# design.net
KiCad netlist of a schematic drawn in Altium Designer
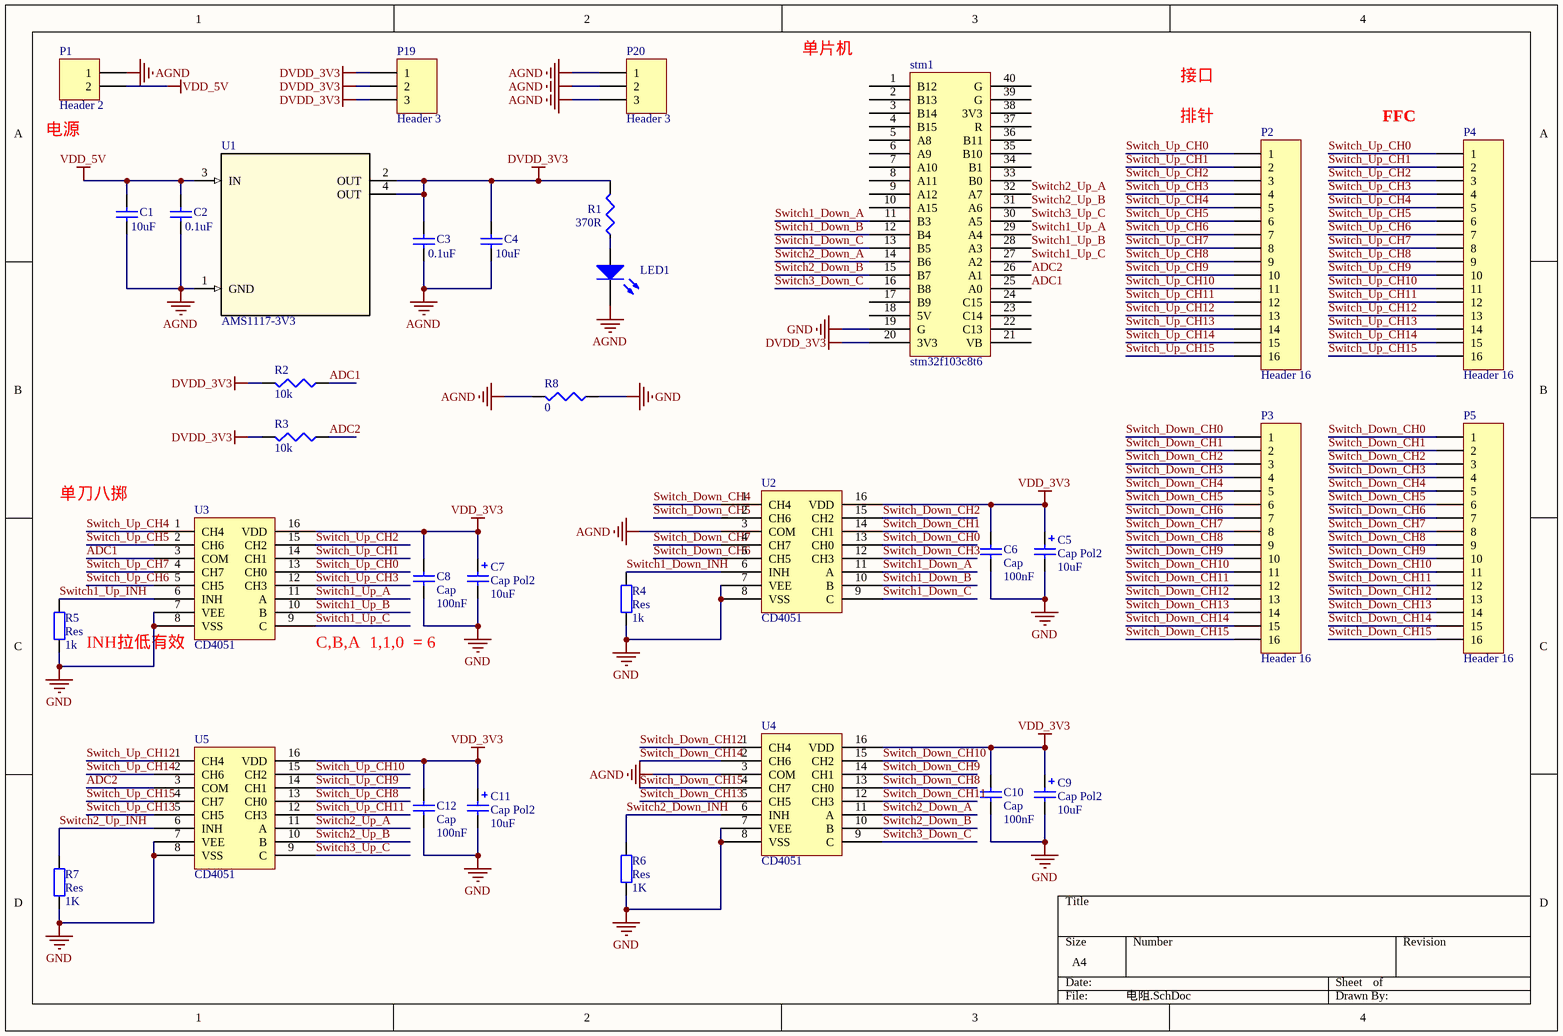
[diagram p0: 电阻.SchDoc]

(export (version "E")
  (design (tool "Eeschema 10.0.6"))
  (components
    (comp (ref "C1")
      (value "10uF")
      (footprint "C-0603")
      (description "Capacitor (Semiconductor SIM Model)")
      (fields (field (name "PUBLISHER") "Altium Limited"))
      (libsource (lib "Miscellaneous Devices") (part "Cap Semi"))
    )
    (comp (ref "C2")
      (value "0.1uF")
      (footprint "C-0603")
      (description "Capacitor (Semiconductor SIM Model)")
      (fields (field (name "PUBLISHER") "Altium Limited"))
      (libsource (lib "Miscellaneous Devices") (part "Cap Semi"))
    )
    (comp (ref "C3")
      (value "0.1uF")
      (footprint "C-0603")
      (description "Capacitor (Semiconductor SIM Model)")
      (fields (field (name "PUBLISHER") "Altium Limited"))
      (libsource (lib "Miscellaneous Devices") (part "Cap Semi"))
    )
    (comp (ref "C4")
      (value "10uF")
      (footprint "C-0603")
      (description "Capacitor (Semiconductor SIM Model)")
      (fields (field (name "PUBLISHER") "Altium Limited"))
      (libsource (lib "Miscellaneous Devices") (part "Cap Semi"))
    )
    (comp (ref "C5")
      (value "Cap Pol2")
      (footprint "Cap-TA")
      (description "Polarized Capacitor (Axial)")
      (fields (field (name "ALTIUM_VALUE") "10uF") (field (name "PUBLISHER") "Altium Limited"))
      (libsource (lib "YD-LibrarySCH") (part "Cap Pol2"))
    )
    (comp (ref "C6")
      (value "Cap")
      (footprint "0805C")
      (description "Capacitor")
      (fields (field (name "ALTIUM_VALUE") "100nF") (field (name "PUBLISHER") "Altium Limited"))
      (libsource (lib "YD-LibrarySCH") (part "Cap"))
    )
    (comp (ref "C7")
      (value "Cap Pol2")
      (footprint "Cap-TA")
      (description "Polarized Capacitor (Axial)")
      (fields (field (name "ALTIUM_VALUE") "10uF") (field (name "PUBLISHER") "Altium Limited"))
      (libsource (lib "YD-LibrarySCH") (part "Cap Pol2"))
    )
    (comp (ref "C8")
      (value "Cap")
      (footprint "0805C")
      (description "Capacitor")
      (fields (field (name "ALTIUM_VALUE") "100nF") (field (name "PUBLISHER") "Altium Limited"))
      (libsource (lib "YD-LibrarySCH") (part "Cap"))
    )
    (comp (ref "C9")
      (value "Cap Pol2")
      (footprint "Cap-TA")
      (description "Polarized Capacitor (Axial)")
      (fields (field (name "ALTIUM_VALUE") "10uF") (field (name "PUBLISHER") "Altium Limited"))
      (libsource (lib "YD-LibrarySCH") (part "Cap Pol2"))
    )
    (comp (ref "C10")
      (value "Cap")
      (footprint "0805C")
      (description "Capacitor")
      (fields (field (name "ALTIUM_VALUE") "100nF") (field (name "PUBLISHER") "Altium Limited"))
      (libsource (lib "YD-LibrarySCH") (part "Cap"))
    )
    (comp (ref "C11")
      (value "Cap Pol2")
      (footprint "Cap-TA")
      (description "Polarized Capacitor (Axial)")
      (fields (field (name "ALTIUM_VALUE") "10uF") (field (name "PUBLISHER") "Altium Limited"))
      (libsource (lib "YD-LibrarySCH") (part "Cap Pol2"))
    )
    (comp (ref "C12")
      (value "Cap")
      (footprint "0805C")
      (description "Capacitor")
      (fields (field (name "ALTIUM_VALUE") "100nF") (field (name "PUBLISHER") "Altium Limited"))
      (libsource (lib "YD-LibrarySCH") (part "Cap"))
    )
    (comp (ref "LED1")
      (value "~")
      (footprint "CLED1608-0603")
      (description "Typical Chip LED")
      (fields (field (name "PUBLISHER") "Altium Limited"))
      (libsource (lib "EButterflyIntegratedLibrary") (part "LED Chip"))
    )
    (comp (ref "P1")
      (value "Header 2")
      (footprint "XH2.54-LI-2P")
      (description "Header, 2-Pin")
      (fields (field (name "PUBLISHER") "Altium Limited"))
      (libsource (lib "Miscellaneous Connectors") (part "Header 2"))
    )
    (comp (ref "P2")
      (value "Header 16")
      (footprint "HDR1X16")
      (description "Header, 16-Pin")
      (fields (field (name "PUBLISHER") "Altium Limited"))
      (libsource (lib "Miscellaneous Connectors") (part "Header 16"))
    )
    (comp (ref "P3")
      (value "Header 16")
      (footprint "HDR1X16")
      (description "Header, 16-Pin")
      (fields (field (name "PUBLISHER") "Altium Limited"))
      (libsource (lib "Miscellaneous Connectors") (part "Header 16"))
    )
    (comp (ref "P4")
      (value "Header 16")
      (footprint "ffc_1mm")
      (description "Header, 16-Pin")
      (fields (field (name "PUBLISHER") "Altium Limited"))
      (libsource (lib "Miscellaneous Connectors") (part "Header 16"))
    )
    (comp (ref "P5")
      (value "Header 16")
      (footprint "ffc_1mm")
      (description "Header, 16-Pin")
      (fields (field (name "PUBLISHER") "Altium Limited"))
      (libsource (lib "Miscellaneous Connectors") (part "Header 16"))
    )
    (comp (ref "P19")
      (value "Header 3")
      (footprint "HDR1X3")
      (description "Header, 3-Pin")
      (fields (field (name "PUBLISHER") "Altium Limited"))
      (libsource (lib "Miscellaneous Connectors") (part "Header 3"))
    )
    (comp (ref "P20")
      (value "Header 3")
      (footprint "HDR1X3")
      (description "Header, 3-Pin")
      (fields (field (name "PUBLISHER") "Altium Limited"))
      (libsource (lib "Miscellaneous Connectors") (part "Header 3"))
    )
    (comp (ref "R1")
      (value "370R")
      (footprint "R-0603")
      (description "Resistor")
      (fields (field (name "Comment") "Res3") (field (name "PUBLISHER") "Altium Limited"))
      (libsource (lib "Miscellaneous Devices") (part "Res3"))
    )
    (comp (ref "R2")
      (value "10k")
      (footprint "R-0603")
      (description "Resistor")
      (fields (field (name "Comment") "Res3") (field (name "PUBLISHER") "Altium Limited"))
      (libsource (lib "Miscellaneous Devices") (part "Res3"))
    )
    (comp (ref "R3")
      (value "10k")
      (footprint "R-0603")
      (description "Resistor")
      (fields (field (name "Comment") "Res3") (field (name "PUBLISHER") "Altium Limited"))
      (libsource (lib "Miscellaneous Devices") (part "Res3"))
    )
    (comp (ref "R4")
      (value "Res")
      (footprint "0805R")
      (description "Resistor")
      (fields (field (name "ALTIUM_VALUE") "1k") (field (name "PUBLISHER") "Altium Limited"))
      (libsource (lib "YD-LibrarySCH") (part "Res"))
    )
    (comp (ref "R5")
      (value "Res")
      (footprint "0805R")
      (description "Resistor")
      (fields (field (name "ALTIUM_VALUE") "1k") (field (name "PUBLISHER") "Altium Limited"))
      (libsource (lib "YD-LibrarySCH") (part "Res"))
    )
    (comp (ref "R6")
      (value "Res")
      (footprint "0805R")
      (description "Resistor")
      (fields (field (name "ALTIUM_VALUE") "1K") (field (name "PUBLISHER") "Altium Limited"))
      (libsource (lib "YD-LibrarySCH") (part "Res"))
    )
    (comp (ref "R7")
      (value "Res")
      (footprint "0805R")
      (description "Resistor")
      (fields (field (name "ALTIUM_VALUE") "1K") (field (name "PUBLISHER") "Altium Limited"))
      (libsource (lib "YD-LibrarySCH") (part "Res"))
    )
    (comp (ref "R8")
      (value "0")
      (footprint "R-0603")
      (description "Resistor")
      (fields (field (name "Comment") "Res3") (field (name "PUBLISHER") "Altium Limited"))
      (libsource (lib "Miscellaneous Devices") (part "Res3"))
    )
    (comp (ref "stm1")
      (value "stm32f103c8t6")
      (footprint "PCBComponent_1")
      (libsource (lib "Schlib1") (part "stm32f103c8t6"))
    )
    (comp (ref "U1")
      (value "AMS1117-3V3")
      (footprint "LM317")
      (description "LM317DCYR-SOT223")
      (fields
        (field (name "PARTNUMBER") "LM317DCYR")
        (field (name "ALTERNATE_PARTNUMBER") "LM317DCY")
        (field (name "SYMBOLCREATER") "Altium")
      )
      (libsource (lib "LM317") (part "LM317DCYR"))
    )
    (comp (ref "U2") (value "CD4051") (footprint "SO16") (libsource (lib "YD-LibrarySCH") (part "CD4051")))
    (comp (ref "U3") (value "CD4051") (footprint "SO16") (libsource (lib "YD-LibrarySCH") (part "CD4051")))
    (comp (ref "U4") (value "CD4051") (footprint "SO16") (libsource (lib "YD-LibrarySCH") (part "CD4051")))
    (comp (ref "U5") (value "CD4051") (footprint "SO16") (libsource (lib "YD-LibrarySCH") (part "CD4051")))
  )
  (nets
    (net (code "1") (name "/ADC1") (class "Default")
      (node (ref "R2") (pin "1") (pinfunction "1_1") (pintype "passive"))
      (node (ref "U3") (pin "3") (pinfunction "COM_3") (pintype "passive"))
      (node (ref "stm1") (pin "25") (pinfunction "A0_25") (pintype "passive"))
    )
    (net (code "2") (name "/ADC2") (class "Default")
      (node (ref "R3") (pin "1") (pinfunction "1_1") (pintype "passive"))
      (node (ref "U5") (pin "3") (pinfunction "COM_3") (pintype "passive"))
      (node (ref "stm1") (pin "26") (pinfunction "A1_26") (pintype "passive"))
    )
    (net (code "6") (name "/Switch1_Down_A") (class "Default")
      (node (ref "U2") (pin "11") (pinfunction "A_11") (pintype "passive"))
      (node (ref "stm1") (pin "11") (pinfunction "B3_11") (pintype "passive"))
    )
    (net (code "7") (name "/Switch1_Down_B") (class "Default")
      (node (ref "U2") (pin "10") (pinfunction "B_10") (pintype "passive"))
      (node (ref "stm1") (pin "12") (pinfunction "B4_12") (pintype "passive"))
    )
    (net (code "8") (name "/Switch1_Down_C") (class "Default")
      (node (ref "U2") (pin "9") (pinfunction "C_9") (pintype "passive"))
      (node (ref "stm1") (pin "13") (pinfunction "B5_13") (pintype "passive"))
    )
    (net (code "9") (name "/Switch1_Down_INH") (class "Default")
      (node (ref "R4") (pin "2") (pinfunction "2_2") (pintype "passive"))
      (node (ref "U2") (pin "6") (pinfunction "INH_6") (pintype "passive"))
    )
    (net (code "10") (name "/Switch1_Up_A") (class "Default")
      (node (ref "U3") (pin "11") (pinfunction "A_11") (pintype "passive"))
      (node (ref "stm1") (pin "29") (pinfunction "A4_29") (pintype "passive"))
    )
    (net (code "11") (name "/Switch1_Up_B") (class "Default")
      (node (ref "U3") (pin "10") (pinfunction "B_10") (pintype "passive"))
      (node (ref "stm1") (pin "28") (pinfunction "A3_28") (pintype "passive"))
    )
    (net (code "12") (name "/Switch1_Up_C") (class "Default")
      (node (ref "U3") (pin "9") (pinfunction "C_9") (pintype "passive"))
      (node (ref "stm1") (pin "27") (pinfunction "A2_27") (pintype "passive"))
    )
    (net (code "13") (name "/Switch1_Up_INH") (class "Default")
      (node (ref "R5") (pin "2") (pinfunction "2_2") (pintype "passive"))
      (node (ref "U3") (pin "6") (pinfunction "INH_6") (pintype "passive"))
    )
    (net (code "14") (name "/Switch2_Down_A") (class "Default")
      (node (ref "U4") (pin "11") (pinfunction "A_11") (pintype "passive"))
      (node (ref "stm1") (pin "14") (pinfunction "B6_14") (pintype "passive"))
    )
    (net (code "15") (name "/Switch2_Down_B") (class "Default")
      (node (ref "U4") (pin "10") (pinfunction "B_10") (pintype "passive"))
      (node (ref "stm1") (pin "15") (pinfunction "B7_15") (pintype "passive"))
    )
    (net (code "16") (name "/Switch2_Down_INH") (class "Default")
      (node (ref "R6") (pin "2") (pinfunction "2_2") (pintype "passive"))
      (node (ref "U4") (pin "6") (pinfunction "INH_6") (pintype "passive"))
    )
    (net (code "17") (name "/Switch2_Up_A") (class "Default")
      (node (ref "U5") (pin "11") (pinfunction "A_11") (pintype "passive"))
      (node (ref "stm1") (pin "32") (pinfunction "A7_32") (pintype "passive"))
    )
    (net (code "18") (name "/Switch2_Up_B") (class "Default")
      (node (ref "U5") (pin "10") (pinfunction "B_10") (pintype "passive"))
      (node (ref "stm1") (pin "31") (pinfunction "A6_31") (pintype "passive"))
    )
    (net (code "19") (name "/Switch2_Up_INH") (class "Default")
      (node (ref "R7") (pin "2") (pinfunction "2_2") (pintype "passive"))
      (node (ref "U5") (pin "6") (pinfunction "INH_6") (pintype "passive"))
    )
    (net (code "20") (name "/Switch3_Down_C") (class "Default")
      (node (ref "U4") (pin "9") (pinfunction "C_9") (pintype "passive"))
      (node (ref "stm1") (pin "16") (pinfunction "B8_16") (pintype "passive"))
    )
    (net (code "21") (name "/Switch3_Up_C") (class "Default")
      (node (ref "U5") (pin "9") (pinfunction "C_9") (pintype "passive"))
      (node (ref "stm1") (pin "30") (pinfunction "A5_30") (pintype "passive"))
    )
    (net (code "22") (name "/Switch_Down_CH0") (class "Default")
      (node (ref "P3") (pin "1") (pinfunction "1_1") (pintype "passive"))
      (node (ref "P5") (pin "1") (pinfunction "1_1") (pintype "passive"))
      (node (ref "U2") (pin "13") (pinfunction "CH0_13") (pintype "passive"))
    )
    (net (code "23") (name "/Switch_Down_CH1") (class "Default")
      (node (ref "P3") (pin "2") (pinfunction "2_2") (pintype "passive"))
      (node (ref "P5") (pin "2") (pinfunction "2_2") (pintype "passive"))
      (node (ref "U2") (pin "14") (pinfunction "CH1_14") (pintype "passive"))
    )
    (net (code "24") (name "/Switch_Down_CH2") (class "Default")
      (node (ref "P3") (pin "3") (pinfunction "3_3") (pintype "passive"))
      (node (ref "P5") (pin "3") (pinfunction "3_3") (pintype "passive"))
      (node (ref "U2") (pin "15") (pinfunction "CH2_15") (pintype "passive"))
    )
    (net (code "25") (name "/Switch_Down_CH3") (class "Default")
      (node (ref "P3") (pin "4") (pinfunction "4_4") (pintype "passive"))
      (node (ref "P5") (pin "4") (pinfunction "4_4") (pintype "passive"))
      (node (ref "U2") (pin "12") (pinfunction "CH3_12") (pintype "passive"))
    )
    (net (code "26") (name "/Switch_Down_CH4") (class "Default")
      (node (ref "P3") (pin "5") (pinfunction "5_5") (pintype "passive"))
      (node (ref "P5") (pin "5") (pinfunction "5_5") (pintype "passive"))
      (node (ref "U2") (pin "1") (pinfunction "CH4_1") (pintype "passive"))
    )
    (net (code "27") (name "/Switch_Down_CH5") (class "Default")
      (node (ref "P3") (pin "6") (pinfunction "6_6") (pintype "passive"))
      (node (ref "P5") (pin "6") (pinfunction "6_6") (pintype "passive"))
      (node (ref "U2") (pin "2") (pinfunction "CH6_2") (pintype "passive"))
    )
    (net (code "28") (name "/Switch_Down_CH6") (class "Default")
      (node (ref "P3") (pin "7") (pinfunction "7_7") (pintype "passive"))
      (node (ref "P5") (pin "7") (pinfunction "7_7") (pintype "passive"))
      (node (ref "U2") (pin "5") (pinfunction "CH5_5") (pintype "passive"))
    )
    (net (code "29") (name "/Switch_Down_CH7") (class "Default")
      (node (ref "P3") (pin "8") (pinfunction "8_8") (pintype "passive"))
      (node (ref "P5") (pin "8") (pinfunction "8_8") (pintype "passive"))
      (node (ref "U2") (pin "4") (pinfunction "CH7_4") (pintype "passive"))
    )
    (net (code "30") (name "/Switch_Down_CH8") (class "Default")
      (node (ref "P3") (pin "9") (pinfunction "9_9") (pintype "passive"))
      (node (ref "P5") (pin "9") (pinfunction "9_9") (pintype "passive"))
      (node (ref "U4") (pin "13") (pinfunction "CH0_13") (pintype "passive"))
    )
    (net (code "31") (name "/Switch_Down_CH9") (class "Default")
      (node (ref "P3") (pin "10") (pinfunction "10_10") (pintype "passive"))
      (node (ref "P5") (pin "10") (pinfunction "10_10") (pintype "passive"))
      (node (ref "U4") (pin "14") (pinfunction "CH1_14") (pintype "passive"))
    )
    (net (code "32") (name "/Switch_Down_CH10") (class "Default")
      (node (ref "P3") (pin "11") (pinfunction "11_11") (pintype "passive"))
      (node (ref "P5") (pin "11") (pinfunction "11_11") (pintype "passive"))
      (node (ref "U4") (pin "15") (pinfunction "CH2_15") (pintype "passive"))
    )
    (net (code "33") (name "/Switch_Down_CH11") (class "Default")
      (node (ref "P3") (pin "12") (pinfunction "12_12") (pintype "passive"))
      (node (ref "P5") (pin "12") (pinfunction "12_12") (pintype "passive"))
      (node (ref "U4") (pin "12") (pinfunction "CH3_12") (pintype "passive"))
    )
    (net (code "34") (name "/Switch_Down_CH12") (class "Default")
      (node (ref "P3") (pin "13") (pinfunction "13_13") (pintype "passive"))
      (node (ref "P5") (pin "13") (pinfunction "13_13") (pintype "passive"))
      (node (ref "U4") (pin "1") (pinfunction "CH4_1") (pintype "passive"))
    )
    (net (code "35") (name "/Switch_Down_CH13") (class "Default")
      (node (ref "P3") (pin "14") (pinfunction "14_14") (pintype "passive"))
      (node (ref "P5") (pin "14") (pinfunction "14_14") (pintype "passive"))
      (node (ref "U4") (pin "5") (pinfunction "CH5_5") (pintype "passive"))
    )
    (net (code "36") (name "/Switch_Down_CH14") (class "Default")
      (node (ref "P3") (pin "15") (pinfunction "15_15") (pintype "passive"))
      (node (ref "P5") (pin "15") (pinfunction "15_15") (pintype "passive"))
      (node (ref "U4") (pin "2") (pinfunction "CH6_2") (pintype "passive"))
    )
    (net (code "37") (name "/Switch_Down_CH15") (class "Default")
      (node (ref "P3") (pin "16") (pinfunction "16_16") (pintype "passive"))
      (node (ref "P5") (pin "16") (pinfunction "16_16") (pintype "passive"))
      (node (ref "U4") (pin "4") (pinfunction "CH7_4") (pintype "passive"))
    )
    (net (code "38") (name "/Switch_Up_CH0") (class "Default")
      (node (ref "P2") (pin "1") (pinfunction "1_1") (pintype "passive"))
      (node (ref "P4") (pin "1") (pinfunction "1_1") (pintype "passive"))
      (node (ref "U3") (pin "13") (pinfunction "CH0_13") (pintype "passive"))
    )
    (net (code "39") (name "/Switch_Up_CH1") (class "Default")
      (node (ref "P2") (pin "2") (pinfunction "2_2") (pintype "passive"))
      (node (ref "P4") (pin "2") (pinfunction "2_2") (pintype "passive"))
      (node (ref "U3") (pin "14") (pinfunction "CH1_14") (pintype "passive"))
    )
    (net (code "40") (name "/Switch_Up_CH2") (class "Default")
      (node (ref "P2") (pin "3") (pinfunction "3_3") (pintype "passive"))
      (node (ref "P4") (pin "3") (pinfunction "3_3") (pintype "passive"))
      (node (ref "U3") (pin "15") (pinfunction "CH2_15") (pintype "passive"))
    )
    (net (code "41") (name "/Switch_Up_CH3") (class "Default")
      (node (ref "P2") (pin "4") (pinfunction "4_4") (pintype "passive"))
      (node (ref "P4") (pin "4") (pinfunction "4_4") (pintype "passive"))
      (node (ref "U3") (pin "12") (pinfunction "CH3_12") (pintype "passive"))
    )
    (net (code "42") (name "/Switch_Up_CH4") (class "Default")
      (node (ref "P2") (pin "5") (pinfunction "5_5") (pintype "passive"))
      (node (ref "P4") (pin "5") (pinfunction "5_5") (pintype "passive"))
      (node (ref "U3") (pin "1") (pinfunction "CH4_1") (pintype "passive"))
    )
    (net (code "43") (name "/Switch_Up_CH5") (class "Default")
      (node (ref "P2") (pin "6") (pinfunction "6_6") (pintype "passive"))
      (node (ref "P4") (pin "6") (pinfunction "6_6") (pintype "passive"))
      (node (ref "U3") (pin "2") (pinfunction "CH6_2") (pintype "passive"))
    )
    (net (code "44") (name "/Switch_Up_CH6") (class "Default")
      (node (ref "P2") (pin "7") (pinfunction "7_7") (pintype "passive"))
      (node (ref "P4") (pin "7") (pinfunction "7_7") (pintype "passive"))
      (node (ref "U3") (pin "5") (pinfunction "CH5_5") (pintype "passive"))
    )
    (net (code "45") (name "/Switch_Up_CH7") (class "Default")
      (node (ref "P2") (pin "8") (pinfunction "8_8") (pintype "passive"))
      (node (ref "P4") (pin "8") (pinfunction "8_8") (pintype "passive"))
      (node (ref "U3") (pin "4") (pinfunction "CH7_4") (pintype "passive"))
    )
    (net (code "46") (name "/Switch_Up_CH8") (class "Default")
      (node (ref "P2") (pin "9") (pinfunction "9_9") (pintype "passive"))
      (node (ref "P4") (pin "9") (pinfunction "9_9") (pintype "passive"))
      (node (ref "U5") (pin "13") (pinfunction "CH0_13") (pintype "passive"))
    )
    (net (code "47") (name "/Switch_Up_CH9") (class "Default")
      (node (ref "P2") (pin "10") (pinfunction "10_10") (pintype "passive"))
      (node (ref "P4") (pin "10") (pinfunction "10_10") (pintype "passive"))
      (node (ref "U5") (pin "14") (pinfunction "CH1_14") (pintype "passive"))
    )
    (net (code "48") (name "/Switch_Up_CH10") (class "Default")
      (node (ref "P2") (pin "11") (pinfunction "11_11") (pintype "passive"))
      (node (ref "P4") (pin "11") (pinfunction "11_11") (pintype "passive"))
      (node (ref "U5") (pin "15") (pinfunction "CH2_15") (pintype "passive"))
    )
    (net (code "49") (name "/Switch_Up_CH11") (class "Default")
      (node (ref "P2") (pin "12") (pinfunction "12_12") (pintype "passive"))
      (node (ref "P4") (pin "12") (pinfunction "12_12") (pintype "passive"))
      (node (ref "U5") (pin "12") (pinfunction "CH3_12") (pintype "passive"))
    )
    (net (code "50") (name "/Switch_Up_CH12") (class "Default")
      (node (ref "P2") (pin "13") (pinfunction "13_13") (pintype "passive"))
      (node (ref "P4") (pin "13") (pinfunction "13_13") (pintype "passive"))
      (node (ref "U5") (pin "1") (pinfunction "CH4_1") (pintype "passive"))
    )
    (net (code "51") (name "/Switch_Up_CH13") (class "Default")
      (node (ref "P2") (pin "14") (pinfunction "14_14") (pintype "passive"))
      (node (ref "P4") (pin "14") (pinfunction "14_14") (pintype "passive"))
      (node (ref "U5") (pin "5") (pinfunction "CH5_5") (pintype "passive"))
    )
    (net (code "52") (name "/Switch_Up_CH14") (class "Default")
      (node (ref "P2") (pin "15") (pinfunction "15_15") (pintype "passive"))
      (node (ref "P4") (pin "15") (pinfunction "15_15") (pintype "passive"))
      (node (ref "U5") (pin "2") (pinfunction "CH6_2") (pintype "passive"))
    )
    (net (code "53") (name "/Switch_Up_CH15") (class "Default")
      (node (ref "P2") (pin "16") (pinfunction "16_16") (pintype "passive"))
      (node (ref "P4") (pin "16") (pinfunction "16_16") (pintype "passive"))
      (node (ref "U5") (pin "4") (pinfunction "CH7_4") (pintype "passive"))
    )
    (net (code "59") (name "AGND") (class "Default")
      (node (ref "C1") (pin "1") (pinfunction "1_1") (pintype "passive"))
      (node (ref "C2") (pin "1") (pinfunction "1_1") (pintype "passive"))
      (node (ref "C3") (pin "1") (pinfunction "1_1") (pintype "passive"))
      (node (ref "C4") (pin "1") (pinfunction "1_1") (pintype "passive"))
      (node (ref "LED1") (pin "2") (pinfunction "K_2") (pintype "passive"))
      (node (ref "P1") (pin "1") (pinfunction "1_1") (pintype "passive"))
      (node (ref "P20") (pin "1") (pinfunction "1_1") (pintype "passive"))
      (node (ref "P20") (pin "2") (pinfunction "2_2") (pintype "passive"))
      (node (ref "P20") (pin "3") (pinfunction "3_3") (pintype "passive"))
      (node (ref "R8") (pin "2") (pinfunction "2_2") (pintype "passive"))
      (node (ref "U1") (pin "1") (pinfunction "GND_1") (pintype "input"))
      (node (ref "U2") (pin "3") (pinfunction "COM_3") (pintype "passive"))
      (node (ref "U4") (pin "3") (pinfunction "COM_3") (pintype "passive"))
    )
    (net (code "60") (name "DVDD_3V3") (class "Default")
      (node (ref "C3") (pin "2") (pinfunction "2_2") (pintype "passive"))
      (node (ref "C4") (pin "2") (pinfunction "2_2") (pintype "passive"))
      (node (ref "P19") (pin "1") (pinfunction "1_1") (pintype "passive"))
      (node (ref "P19") (pin "2") (pinfunction "2_2") (pintype "passive"))
      (node (ref "P19") (pin "3") (pinfunction "3_3") (pintype "passive"))
      (node (ref "R1") (pin "2") (pinfunction "2_2") (pintype "passive"))
      (node (ref "R2") (pin "2") (pinfunction "2_2") (pintype "passive"))
      (node (ref "R3") (pin "2") (pinfunction "2_2") (pintype "passive"))
      (node (ref "U1") (pin "2") (pinfunction "OUT_2") (pintype "passive"))
      (node (ref "U1") (pin "4") (pinfunction "OUT_4") (pintype "passive"))
      (node (ref "stm1") (pin "20") (pinfunction "3V3_20") (pintype "passive"))
    )
    (net (code "61") (name "GND") (class "Default")
      (node (ref "C10") (pin "1") (pinfunction "1_1") (pintype "passive"))
      (node (ref "C11") (pin "2") (pinfunction "2_2") (pintype "passive"))
      (node (ref "C12") (pin "1") (pinfunction "1_1") (pintype "passive"))
      (node (ref "C5") (pin "2") (pinfunction "2_2") (pintype "passive"))
      (node (ref "C6") (pin "1") (pinfunction "1_1") (pintype "passive"))
      (node (ref "C7") (pin "2") (pinfunction "2_2") (pintype "passive"))
      (node (ref "C8") (pin "1") (pinfunction "1_1") (pintype "passive"))
      (node (ref "C9") (pin "2") (pinfunction "2_2") (pintype "passive"))
      (node (ref "R4") (pin "1") (pinfunction "1_1") (pintype "passive"))
      (node (ref "R5") (pin "1") (pinfunction "1_1") (pintype "passive"))
      (node (ref "R6") (pin "1") (pinfunction "1_1") (pintype "passive"))
      (node (ref "R7") (pin "1") (pinfunction "1_1") (pintype "passive"))
      (node (ref "R8") (pin "1") (pinfunction "1_1") (pintype "passive"))
      (node (ref "U2") (pin "7") (pinfunction "VEE_7") (pintype "passive"))
      (node (ref "U2") (pin "8") (pinfunction "VSS_8") (pintype "passive"))
      (node (ref "U3") (pin "7") (pinfunction "VEE_7") (pintype "passive"))
      (node (ref "U3") (pin "8") (pinfunction "VSS_8") (pintype "passive"))
      (node (ref "U4") (pin "7") (pinfunction "VEE_7") (pintype "passive"))
      (node (ref "U4") (pin "8") (pinfunction "VSS_8") (pintype "passive"))
      (node (ref "U5") (pin "7") (pinfunction "VEE_7") (pintype "passive"))
      (node (ref "U5") (pin "8") (pinfunction "VSS_8") (pintype "passive"))
      (node (ref "stm1") (pin "19") (pinfunction "G_19") (pintype "passive"))
    )
    (net (code "62") (name "Net-(LED1-A)") (class "Default")
      (node (ref "LED1") (pin "1") (pinfunction "A_1") (pintype "passive"))
      (node (ref "R1") (pin "1") (pinfunction "1_1") (pintype "passive"))
    )
    (net (code "63") (name "VDD_3V3") (class "Default")
      (node (ref "C10") (pin "2") (pinfunction "2_2") (pintype "passive"))
      (node (ref "C11") (pin "1") (pinfunction "1_1") (pintype "passive"))
      (node (ref "C12") (pin "2") (pinfunction "2_2") (pintype "passive"))
      (node (ref "C5") (pin "1") (pinfunction "1_1") (pintype "passive"))
      (node (ref "C6") (pin "2") (pinfunction "2_2") (pintype "passive"))
      (node (ref "C7") (pin "1") (pinfunction "1_1") (pintype "passive"))
      (node (ref "C8") (pin "2") (pinfunction "2_2") (pintype "passive"))
      (node (ref "C9") (pin "1") (pinfunction "1_1") (pintype "passive"))
      (node (ref "U2") (pin "16") (pinfunction "VDD_16") (pintype "passive"))
      (node (ref "U3") (pin "16") (pinfunction "VDD_16") (pintype "passive"))
      (node (ref "U4") (pin "16") (pinfunction "VDD_16") (pintype "passive"))
      (node (ref "U5") (pin "16") (pinfunction "VDD_16") (pintype "passive"))
    )
    (net (code "64") (name "VDD_5V") (class "Default")
      (node (ref "C1") (pin "2") (pinfunction "2_2") (pintype "passive"))
      (node (ref "C2") (pin "2") (pinfunction "2_2") (pintype "passive"))
      (node (ref "P1") (pin "2") (pinfunction "2_2") (pintype "passive"))
      (node (ref "U1") (pin "3") (pinfunction "IN_3") (pintype "input"))
    )
    (net (code "65") (name "unconnected-(stm1-3V3-Pad38)") (class "Default")
      (node (ref "stm1") (pin "38") (pinfunction "3V3_38") (pintype "passive"))
    )
    (net (code "66") (name "unconnected-(stm1-5V-Pad18)") (class "Default")
      (node (ref "stm1") (pin "18") (pinfunction "5V_18") (pintype "passive"))
    )
    (net (code "67") (name "unconnected-(stm1-A8-Pad5)") (class "Default")
      (node (ref "stm1") (pin "5") (pinfunction "A8_5") (pintype "passive"))
    )
    (net (code "68") (name "unconnected-(stm1-A9-Pad6)") (class "Default")
      (node (ref "stm1") (pin "6") (pinfunction "A9_6") (pintype "passive"))
    )
    (net (code "69") (name "unconnected-(stm1-A10-Pad7)") (class "Default")
      (node (ref "stm1") (pin "7") (pinfunction "A10_7") (pintype "passive"))
    )
    (net (code "70") (name "unconnected-(stm1-A11-Pad8)") (class "Default")
      (node (ref "stm1") (pin "8") (pinfunction "A11_8") (pintype "passive"))
    )
    (net (code "71") (name "unconnected-(stm1-A12-Pad9)") (class "Default")
      (node (ref "stm1") (pin "9") (pinfunction "A12_9") (pintype "passive"))
    )
    (net (code "72") (name "unconnected-(stm1-A15-Pad10)") (class "Default")
      (node (ref "stm1") (pin "10") (pinfunction "A15_10") (pintype "passive"))
    )
    (net (code "73") (name "unconnected-(stm1-B0-Pad33)") (class "Default")
      (node (ref "stm1") (pin "33") (pinfunction "B0_33") (pintype "passive"))
    )
    (net (code "74") (name "unconnected-(stm1-B1-Pad34)") (class "Default")
      (node (ref "stm1") (pin "34") (pinfunction "B1_34") (pintype "passive"))
    )
    (net (code "75") (name "unconnected-(stm1-B9-Pad17)") (class "Default")
      (node (ref "stm1") (pin "17") (pinfunction "B9_17") (pintype "passive"))
    )
    (net (code "76") (name "unconnected-(stm1-B10-Pad35)") (class "Default")
      (node (ref "stm1") (pin "35") (pinfunction "B10_35") (pintype "passive"))
    )
    (net (code "77") (name "unconnected-(stm1-B11-Pad36)") (class "Default")
      (node (ref "stm1") (pin "36") (pinfunction "B11_36") (pintype "passive"))
    )
    (net (code "78") (name "unconnected-(stm1-B12-Pad1)") (class "Default")
      (node (ref "stm1") (pin "1") (pinfunction "B12_1") (pintype "passive"))
    )
    (net (code "79") (name "unconnected-(stm1-B13-Pad2)") (class "Default")
      (node (ref "stm1") (pin "2") (pinfunction "B13_2") (pintype "passive"))
    )
    (net (code "80") (name "unconnected-(stm1-B14-Pad3)") (class "Default")
      (node (ref "stm1") (pin "3") (pinfunction "B14_3") (pintype "passive"))
    )
    (net (code "81") (name "unconnected-(stm1-B15-Pad4)") (class "Default")
      (node (ref "stm1") (pin "4") (pinfunction "B15_4") (pintype "passive"))
    )
    (net (code "82") (name "unconnected-(stm1-C13-Pad22)") (class "Default")
      (node (ref "stm1") (pin "22") (pinfunction "C13_22") (pintype "passive"))
    )
    (net (code "83") (name "unconnected-(stm1-C14-Pad23)") (class "Default")
      (node (ref "stm1") (pin "23") (pinfunction "C14_23") (pintype "passive"))
    )
    (net (code "84") (name "unconnected-(stm1-C15-Pad24)") (class "Default")
      (node (ref "stm1") (pin "24") (pinfunction "C15_24") (pintype "passive"))
    )
    (net (code "85") (name "unconnected-(stm1-G-Pad39)") (class "Default")
      (node (ref "stm1") (pin "39") (pinfunction "G_39") (pintype "passive"))
    )
    (net (code "86") (name "unconnected-(stm1-G-Pad40)") (class "Default")
      (node (ref "stm1") (pin "40") (pinfunction "G_40") (pintype "passive"))
    )
    (net (code "87") (name "unconnected-(stm1-R-Pad37)") (class "Default")
      (node (ref "stm1") (pin "37") (pinfunction "R_37") (pintype "passive"))
    )
    (net (code "88") (name "unconnected-(stm1-VB-Pad21)") (class "Default")
      (node (ref "stm1") (pin "21") (pinfunction "VB_21") (pintype "passive"))
    )
  )
)
